# ATXBreakout.net
KiCad netlist of a schematic drawn in EAGLE
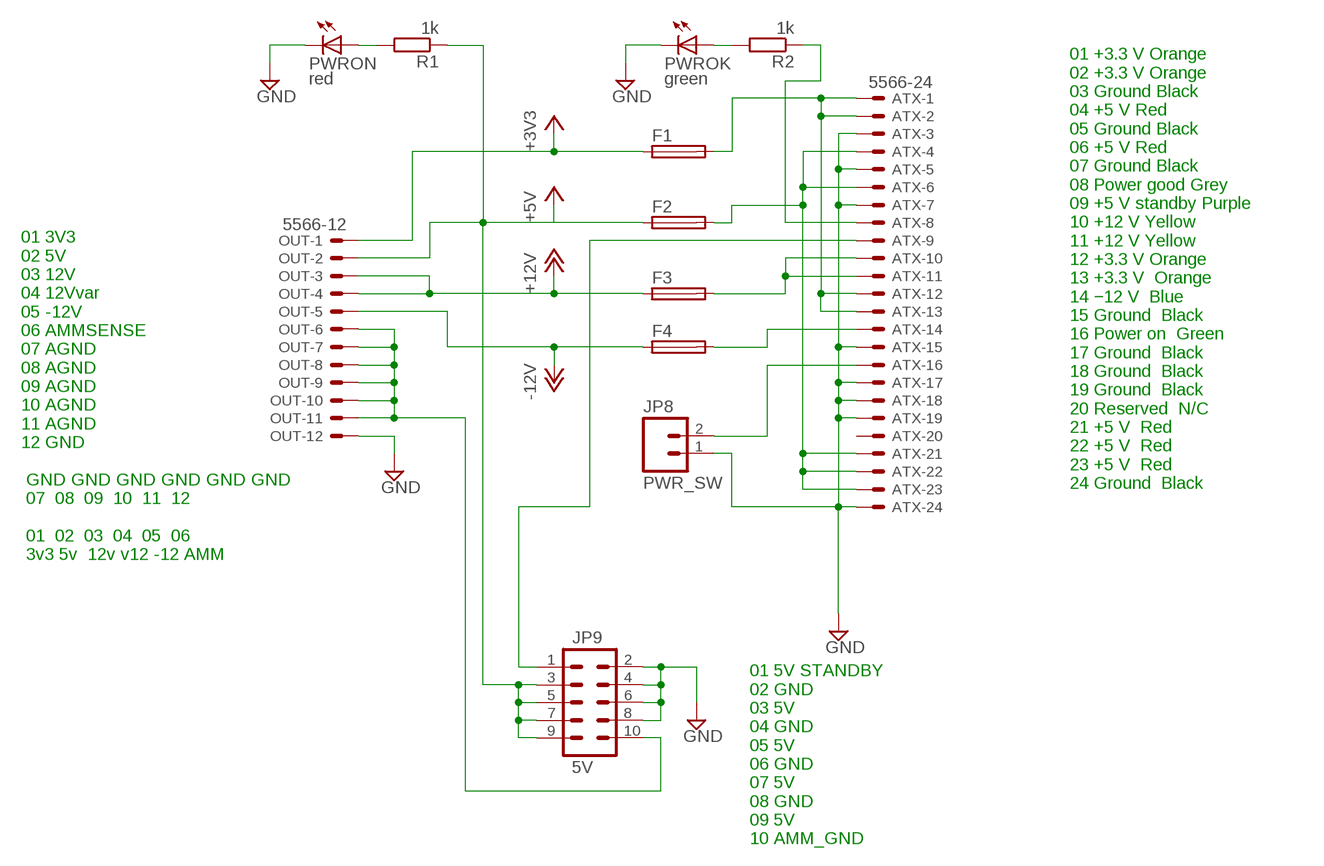
[diagram p0: schematic, sheet 1]

(export (version "E")
  (design (tool "Eeschema 10.0.6"))
  (components
    (comp (ref "ATX")
      (value "5566-24")
      (footprint "eagle-import:5566-24")
      (libsource (lib "eagle-import") (part "5566-24"))
    )
    (comp (ref "F1")
      (value "FUSESHK20Q")
      (footprint "eagle-import:SHK20Q")
      (libsource (lib "eagle-import") (part "FUSESHK20Q"))
    )
    (comp (ref "F2")
      (value "FUSESHK20Q")
      (footprint "eagle-import:SHK20Q")
      (libsource (lib "eagle-import") (part "FUSESHK20Q"))
    )
    (comp (ref "F3")
      (value "FUSESHK20Q")
      (footprint "eagle-import:SHK20Q")
      (libsource (lib "eagle-import") (part "FUSESHK20Q"))
    )
    (comp (ref "F4")
      (value "FUSESHK20Q")
      (footprint "eagle-import:SHK20Q")
      (libsource (lib "eagle-import") (part "FUSESHK20Q"))
    )
    (comp (ref "JP8")
      (value "PWR_SW")
      (footprint "eagle-import:1X02")
      (libsource (lib "eagle-import") (part "M02PTH"))
    )
    (comp (ref "JP9")
      (value "5V")
      (footprint "eagle-import:AVR_ICSP")
      (libsource (lib "eagle-import") (part "M05X2PTH"))
    )
    (comp (ref "OUT")
      (value "5566-12")
      (footprint "eagle-import:5566-12")
      (libsource (lib "eagle-import") (part "5566-12"))
    )
    (comp (ref "PWROK")
      (value "green")
      (footprint "eagle-import:LED5MM")
      (libsource (lib "eagle-import") (part "LED5MM"))
    )
    (comp (ref "PWRON")
      (value "red")
      (footprint "eagle-import:LED5MM")
      (libsource (lib "eagle-import") (part "LED5MM"))
    )
    (comp (ref "R1")
      (value "1k")
      (footprint "eagle-import:0204_7")
      (libsource (lib "eagle-import") (part "R-EU_0204/7"))
    )
    (comp (ref "R2")
      (value "1k")
      (footprint "eagle-import:0204_7")
      (libsource (lib "eagle-import") (part "R-EU_0204/7"))
    )
  )
  (nets
    (net (code "1") (name "+3V3") (class "Default")
      (node (ref "F1") (pin "1A") (pinfunction "1_1A") (pintype "passive"))
      (node (ref "OUT") (pin "1") (pinfunction "S_1") (pintype "passive"))
    )
    (net (code "2") (name "+5V") (class "Default")
      (node (ref "F2") (pin "1A") (pinfunction "1_1A") (pintype "passive"))
      (node (ref "JP9") (pin "3") (pinfunction "3_3") (pintype "passive"))
      (node (ref "JP9") (pin "5") (pinfunction "5_5") (pintype "passive"))
      (node (ref "JP9") (pin "7") (pinfunction "7_7") (pintype "passive"))
      (node (ref "JP9") (pin "9") (pinfunction "9_9") (pintype "passive"))
      (node (ref "OUT") (pin "2") (pinfunction "S_2") (pintype "passive"))
      (node (ref "R1") (pin "1") (pinfunction "1_1") (pintype "passive"))
    )
    (net (code "3") (name "+12V") (class "Default")
      (node (ref "F3") (pin "1A") (pinfunction "1_1A") (pintype "passive"))
      (node (ref "OUT") (pin "3") (pinfunction "S_3") (pintype "passive"))
      (node (ref "OUT") (pin "4") (pinfunction "S_4") (pintype "passive"))
    )
    (net (code "4") (name "-12V") (class "Default")
      (node (ref "F4") (pin "1A") (pinfunction "1_1A") (pintype "passive"))
      (node (ref "OUT") (pin "5") (pinfunction "S_5") (pintype "passive"))
    )
    (net (code "5") (name "GND") (class "Default")
      (node (ref "ATX") (pin "15") (pinfunction "S_15") (pintype "passive"))
      (node (ref "ATX") (pin "17") (pinfunction "S_17") (pintype "passive"))
      (node (ref "ATX") (pin "18") (pinfunction "S_18") (pintype "passive"))
      (node (ref "ATX") (pin "19") (pinfunction "S_19") (pintype "passive"))
      (node (ref "ATX") (pin "24") (pinfunction "S_24") (pintype "passive"))
      (node (ref "ATX") (pin "3") (pinfunction "S_3") (pintype "passive"))
      (node (ref "ATX") (pin "5") (pinfunction "S_5") (pintype "passive"))
      (node (ref "ATX") (pin "7") (pinfunction "S_7") (pintype "passive"))
      (node (ref "JP8") (pin "1") (pinfunction "1_1") (pintype "passive"))
      (node (ref "JP9") (pin "2") (pinfunction "2_2") (pintype "passive"))
      (node (ref "JP9") (pin "4") (pinfunction "4_4") (pintype "passive"))
      (node (ref "JP9") (pin "6") (pinfunction "6_6") (pintype "passive"))
      (node (ref "JP9") (pin "8") (pinfunction "8_8") (pintype "passive"))
      (node (ref "OUT") (pin "12") (pinfunction "S_12") (pintype "passive"))
      (node (ref "PWROK") (pin "K") (pinfunction "C_K") (pintype "passive"))
      (node (ref "PWRON") (pin "K") (pinfunction "C_K") (pintype "passive"))
    )
    (net (code "6") (name "Net-(ATXA-S)") (class "Default")
      (node (ref "ATX") (pin "1") (pinfunction "S_1") (pintype "passive"))
      (node (ref "ATX") (pin "12") (pinfunction "S_12") (pintype "passive"))
      (node (ref "ATX") (pin "13") (pinfunction "S_13") (pintype "passive"))
      (node (ref "ATX") (pin "2") (pinfunction "S_2") (pintype "passive"))
      (node (ref "F1") (pin "2A") (pinfunction "2_2A") (pintype "passive"))
    )
    (net (code "7") (name "Net-(ATXB-S)") (class "Default")
      (node (ref "ATX") (pin "10") (pinfunction "S_10") (pintype "passive"))
      (node (ref "ATX") (pin "11") (pinfunction "S_11") (pintype "passive"))
      (node (ref "F3") (pin "2A") (pinfunction "2_2A") (pintype "passive"))
    )
    (net (code "8") (name "Net-(ATXF-S)") (class "Default")
      (node (ref "ATX") (pin "14") (pinfunction "S_14") (pintype "passive"))
      (node (ref "F4") (pin "2A") (pinfunction "2_2A") (pintype "passive"))
    )
    (net (code "9") (name "Net-(ATXH-S)") (class "Default")
      (node (ref "ATX") (pin "16") (pinfunction "S_16") (pintype "passive"))
      (node (ref "JP8") (pin "2") (pinfunction "2_2") (pintype "passive"))
    )
    (net (code "10") (name "Net-(ATXN-S)") (class "Default")
      (node (ref "ATX") (pin "21") (pinfunction "S_21") (pintype "passive"))
      (node (ref "ATX") (pin "22") (pinfunction "S_22") (pintype "passive"))
      (node (ref "ATX") (pin "23") (pinfunction "S_23") (pintype "passive"))
      (node (ref "ATX") (pin "4") (pinfunction "S_4") (pintype "passive"))
      (node (ref "ATX") (pin "6") (pinfunction "S_6") (pintype "passive"))
      (node (ref "F2") (pin "2A") (pinfunction "2_2A") (pintype "passive"))
    )
    (net (code "11") (name "Net-(ATXW-S)") (class "Default")
      (node (ref "ATX") (pin "8") (pinfunction "S_8") (pintype "passive"))
      (node (ref "R2") (pin "1") (pinfunction "1_1") (pintype "passive"))
    )
    (net (code "12") (name "Net-(ATXX-S)") (class "Default")
      (node (ref "ATX") (pin "9") (pinfunction "S_9") (pintype "passive"))
      (node (ref "JP9") (pin "1") (pinfunction "1_1") (pintype "passive"))
    )
    (net (code "13") (name "Net-(OUTB-S)") (class "Default")
      (node (ref "JP9") (pin "10") (pinfunction "10_10") (pintype "passive"))
      (node (ref "OUT") (pin "10") (pinfunction "S_10") (pintype "passive"))
      (node (ref "OUT") (pin "11") (pinfunction "S_11") (pintype "passive"))
      (node (ref "OUT") (pin "6") (pinfunction "S_6") (pintype "passive"))
      (node (ref "OUT") (pin "7") (pinfunction "S_7") (pintype "passive"))
      (node (ref "OUT") (pin "8") (pinfunction "S_8") (pintype "passive"))
      (node (ref "OUT") (pin "9") (pinfunction "S_9") (pintype "passive"))
    )
    (net (code "14") (name "Net-(PWROK-PadA)") (class "Default")
      (node (ref "PWROK") (pin "A") (pinfunction "A_A") (pintype "passive"))
      (node (ref "R2") (pin "2") (pinfunction "2_2") (pintype "passive"))
    )
    (net (code "15") (name "Net-(PWRON-PadA)") (class "Default")
      (node (ref "PWRON") (pin "A") (pinfunction "A_A") (pintype "passive"))
      (node (ref "R1") (pin "2") (pinfunction "2_2") (pintype "passive"))
    )
    (net (code "16") (name "unconnected-(ATXM-S-Pad20)") (class "Default")
      (node (ref "ATX") (pin "20") (pinfunction "S_20") (pintype "passive"))
    )
  )
)
